# SY8003ADFC_3.net
KiCad netlist of a schematic drawn in Altium Designer
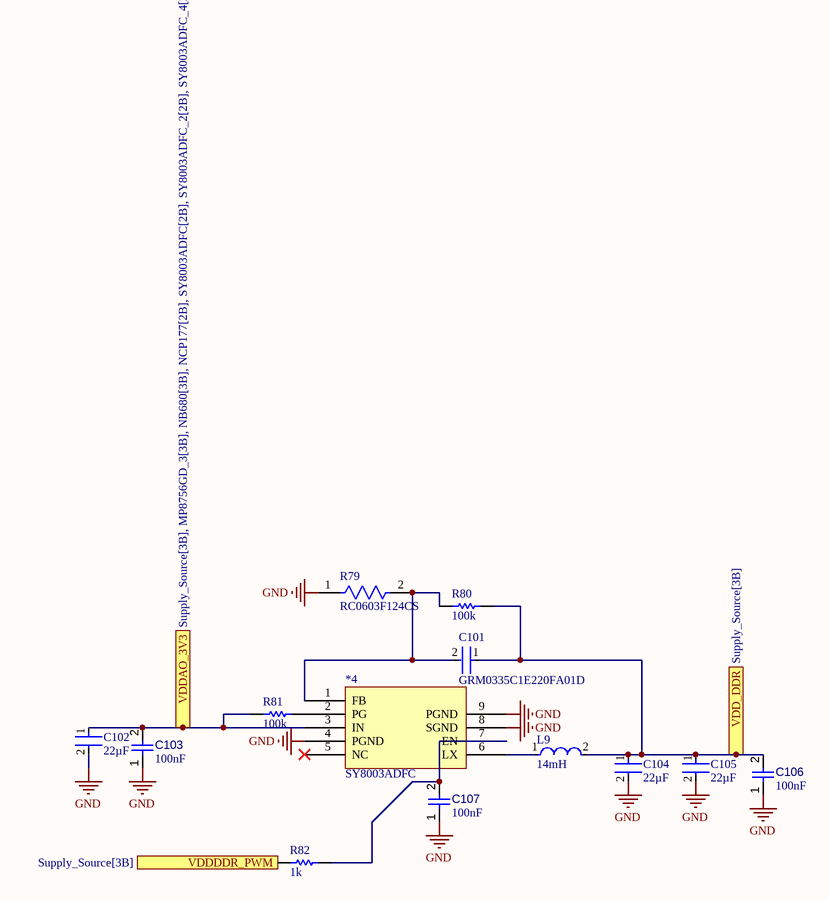
[diagram p0: SY8003ADFC_3.SchDoc]

(export (version "E")
  (design (tool "Eeschema 10.0.6"))
  (components
    (comp (ref "*4")
      (value "SY8003ADFC")
      (footprint "SON127P750X265-8N")
      (description "Switching Regulator, 3A, 1200kHz Switching Freq-Max, PDSO8")
      (libsource (lib "MIGUEL ANGEL ALVAREZ GUZMAN") (part "SY8003ADFC-Symbol-1"))
    )
    (comp (ref "C101")
      (value "GRM0335C1E220FA01D")
      (footprint "FP-GRM033-0_03-IPC_C")
      (description "Chip Multilayer Ceramic Capacitors for General Purpose, 0201, 22pF, C0G, 30ppm/°C, 1%, 25V")
      (fields (field (name "TOLERANCE") "1%"))
      (libsource (lib "Altium Content Vault") (part "b4654b650e69147ec39a6b967a45e02"))
    )
    (comp (ref "C102")
      (value "22µF")
      (footprint "FP-GRM186-0_2-IPC_A")
      (description "6.3V 22uF X5R ±20% 0603 Multilayer Ceramic Capacitors MLCC - SMD/SMT ROHS")
      (fields (field (name "TOLERANCE") "20%") (field (name "Comment") "GRM186R60J226ME15D"))
      (libsource (lib "MIGUEL ANGEL ALVAREZ GUZMAN") (part "02cd4be3c70576c341d710602a673aa"))
    )
    (comp (ref "C103")
      (value "100nF")
      (footprint "CAPC1005X56X25LL10T15")
      (description "Chip Capacitor, 0.1 uF, +/- 5%, 16 V, 0402 (1005 Metric)")
      (fields (field (name "TOLERANCE") "5%") (field (name "Comment") "Capacitor 0.1 uF +/- 5% 16 V 0402"))
      (libsource (lib "MIGUEL ANGEL ALVAREZ GUZMAN") (part "CAP-NP-2"))
    )
    (comp (ref "C104")
      (value "22µF")
      (footprint "FP-GRM186-0_2-IPC_A")
      (description "6.3V 22uF X5R ±20% 0603 Multilayer Ceramic Capacitors MLCC - SMD/SMT ROHS")
      (fields (field (name "TOLERANCE") "20%") (field (name "Comment") "GRM186R60J226ME15D"))
      (libsource (lib "MIGUEL ANGEL ALVAREZ GUZMAN") (part "02cd4be3c70576c341d710602a673aa"))
    )
    (comp (ref "C105")
      (value "22µF")
      (footprint "FP-GRM186-0_2-IPC_A")
      (description "6.3V 22uF X5R ±20% 0603 Multilayer Ceramic Capacitors MLCC - SMD/SMT ROHS")
      (fields (field (name "TOLERANCE") "20%") (field (name "Comment") "GRM186R60J226ME15D"))
      (libsource (lib "MIGUEL ANGEL ALVAREZ GUZMAN") (part "02cd4be3c70576c341d710602a673aa"))
    )
    (comp (ref "C106")
      (value "100nF")
      (footprint "CAPC1005X56X25LL10T15")
      (description "Chip Capacitor, 0.1 uF, +/- 5%, 16 V, 0402 (1005 Metric)")
      (fields (field (name "TOLERANCE") "5%") (field (name "Comment") "Capacitor 0.1 uF +/- 5% 16 V 0402"))
      (libsource (lib "MIGUEL ANGEL ALVAREZ GUZMAN") (part "CAP-NP-2"))
    )
    (comp (ref "C107")
      (value "100nF")
      (footprint "CAPC1005X56X25LL10T15")
      (description "Chip Capacitor, 0.1 uF, +/- 5%, 16 V, 0402 (1005 Metric)")
      (fields (field (name "TOLERANCE") "5%") (field (name "Comment") "Capacitor 0.1 uF +/- 5% 16 V 0402"))
      (libsource (lib "MIGUEL ANGEL ALVAREZ GUZMAN") (part "CAP-NP-2"))
    )
    (comp (ref "L9")
      (value "14mH")
      (footprint "FP-IHLP-2525CZ-FP_2_413x3-MFG")
      (description "Inductor High Current Shielded Wirewound 1.5uH 20% 100KHz 9A 15mOhm DCR 2525 T/R")
      (fields (field (name "TOLERANCE") "20%") (field (name "Comment") "IHLP2525CZER1R5M01"))
      (libsource (lib "MIGUEL ANGEL ALVAREZ GUZMAN") (part "725321dda6339637d4d059423bc1c3c"))
    )
    (comp (ref "R79")
      (value "RC0603F124CS")
      (footprint "FP-RC0603-MFG")
      (description "Res Thick Film 0201 120kΩ 1% 0.05W ±250ppm/°C Molded SMD T/R")
      (fields (field (name "TOLERANCE") "1%"))
      (libsource (lib "Altium Content Vault") (part "1029c3af85768c4190bb7ad29bc67b5"))
    )
    (comp (ref "R80")
      (value "100k")
      (footprint "RESC0603X26X15NL03T05")
      (description "Res General Purpose Thick Film 0201 100k Ohm 1% 1/20W ±200ppm/°C Molded Paper T/R")
      (fields (field (name "TOLERANCE") "1%") (field (name "Comment") "CRG0201F100K"))
      (libsource (lib "MIGUEL ANGEL ALVAREZ GUZMAN") (part "RES"))
    )
    (comp (ref "R81")
      (value "100k")
      (footprint "RESC0603X26X15NL03T05")
      (description "Res General Purpose Thick Film 0201 100k Ohm 1% 1/20W ±200ppm/°C Molded Paper T/R")
      (fields (field (name "TOLERANCE") "1%") (field (name "Comment") "CRG0201F100K"))
      (libsource (lib "MIGUEL ANGEL ALVAREZ GUZMAN") (part "RES"))
    )
    (comp (ref "R82")
      (value "1k")
      (footprint "RESC0603X26X15NL03T05")
      (description "Res General Purpose Thick Film 0201 1k Ohm 1% 1/20W ±200ppm/°C Molded Paper T/R")
      (fields (field (name "TOLERANCE") "1%") (field (name "Comment") "MCRE000140"))
      (libsource (lib "MIGUEL ANGEL ALVAREZ GUZMAN") (part "RES"))
    )
  )
  (nets
    (net (code "1") (name "/VDDAO_3V3") (class "Default")
      (node (ref "*4") (pin "3") (pinfunction "IN_3") (pintype "passive"))
      (node (ref "C102") (pin "1") (pinfunction "1_1") (pintype "passive"))
      (node (ref "C103") (pin "2") (pinfunction "2_2") (pintype "passive"))
      (node (ref "R81") (pin "1") (pinfunction "1_1") (pintype "passive"))
    )
    (net (code "2") (name "/VDDDDR_PWM") (class "Default")
      (node (ref "R82") (pin "1") (pinfunction "1_1") (pintype "passive"))
    )
    (net (code "3") (name "/VDD_DDR") (class "Default")
      (node (ref "C101") (pin "1") (pinfunction "1_1") (pintype "passive"))
      (node (ref "C104") (pin "1") (pinfunction "1_1") (pintype "passive"))
      (node (ref "C105") (pin "1") (pinfunction "1_1") (pintype "passive"))
      (node (ref "C106") (pin "2") (pinfunction "2_2") (pintype "passive"))
      (node (ref "L9") (pin "2") (pinfunction "2_2") (pintype "passive"))
      (node (ref "R80") (pin "2") (pinfunction "2_2") (pintype "passive"))
    )
    (net (code "4") (name "GND") (class "Default")
      (node (ref "*4") (pin "4") (pinfunction "PGND_4") (pintype "passive"))
      (node (ref "*4") (pin "8") (pinfunction "SGND_8") (pintype "passive"))
      (node (ref "*4") (pin "9") (pinfunction "PGND_9") (pintype "passive"))
      (node (ref "C102") (pin "2") (pinfunction "2_2") (pintype "passive"))
      (node (ref "C103") (pin "1") (pinfunction "1_1") (pintype "passive"))
      (node (ref "C104") (pin "2") (pinfunction "2_2") (pintype "passive"))
      (node (ref "C105") (pin "2") (pinfunction "2_2") (pintype "passive"))
      (node (ref "C106") (pin "1") (pinfunction "1_1") (pintype "passive"))
      (node (ref "C107") (pin "1") (pinfunction "1_1") (pintype "passive"))
      (node (ref "R79") (pin "1") (pinfunction "1_1") (pintype "passive"))
    )
    (net (code "5") (name "Net-(*4-EN)") (class "Default")
      (node (ref "*4") (pin "7") (pinfunction "EN_7") (pintype "passive"))
      (node (ref "C107") (pin "2") (pinfunction "2_2") (pintype "passive"))
      (node (ref "R82") (pin "2") (pinfunction "2_2") (pintype "passive"))
    )
    (net (code "6") (name "Net-(*4-FB)") (class "Default")
      (node (ref "*4") (pin "1") (pinfunction "FB_1") (pintype "passive"))
      (node (ref "C101") (pin "2") (pinfunction "2_2") (pintype "passive"))
      (node (ref "R79") (pin "2") (pinfunction "2_2") (pintype "passive"))
      (node (ref "R80") (pin "1") (pinfunction "1_1") (pintype "passive"))
    )
    (net (code "7") (name "Net-(*4-LX)") (class "Default")
      (node (ref "*4") (pin "6") (pinfunction "LX_6") (pintype "passive"))
      (node (ref "L9") (pin "1") (pinfunction "1_1") (pintype "passive"))
    )
    (net (code "8") (name "Net-(*4-PG)") (class "Default")
      (node (ref "*4") (pin "2") (pinfunction "PG_2") (pintype "passive"))
      (node (ref "R81") (pin "2") (pinfunction "2_2") (pintype "passive"))
    )
    (net (code "9") (name "unconnected-(*4-NC-Pad5)") (class "Default")
      (node (ref "*4") (pin "5") (pinfunction "NC_5") (pintype "passive+no_connect"))
    )
  )
)
